# transition_pcb.net
KiCad netlist of a schematic drawn in EAGLE
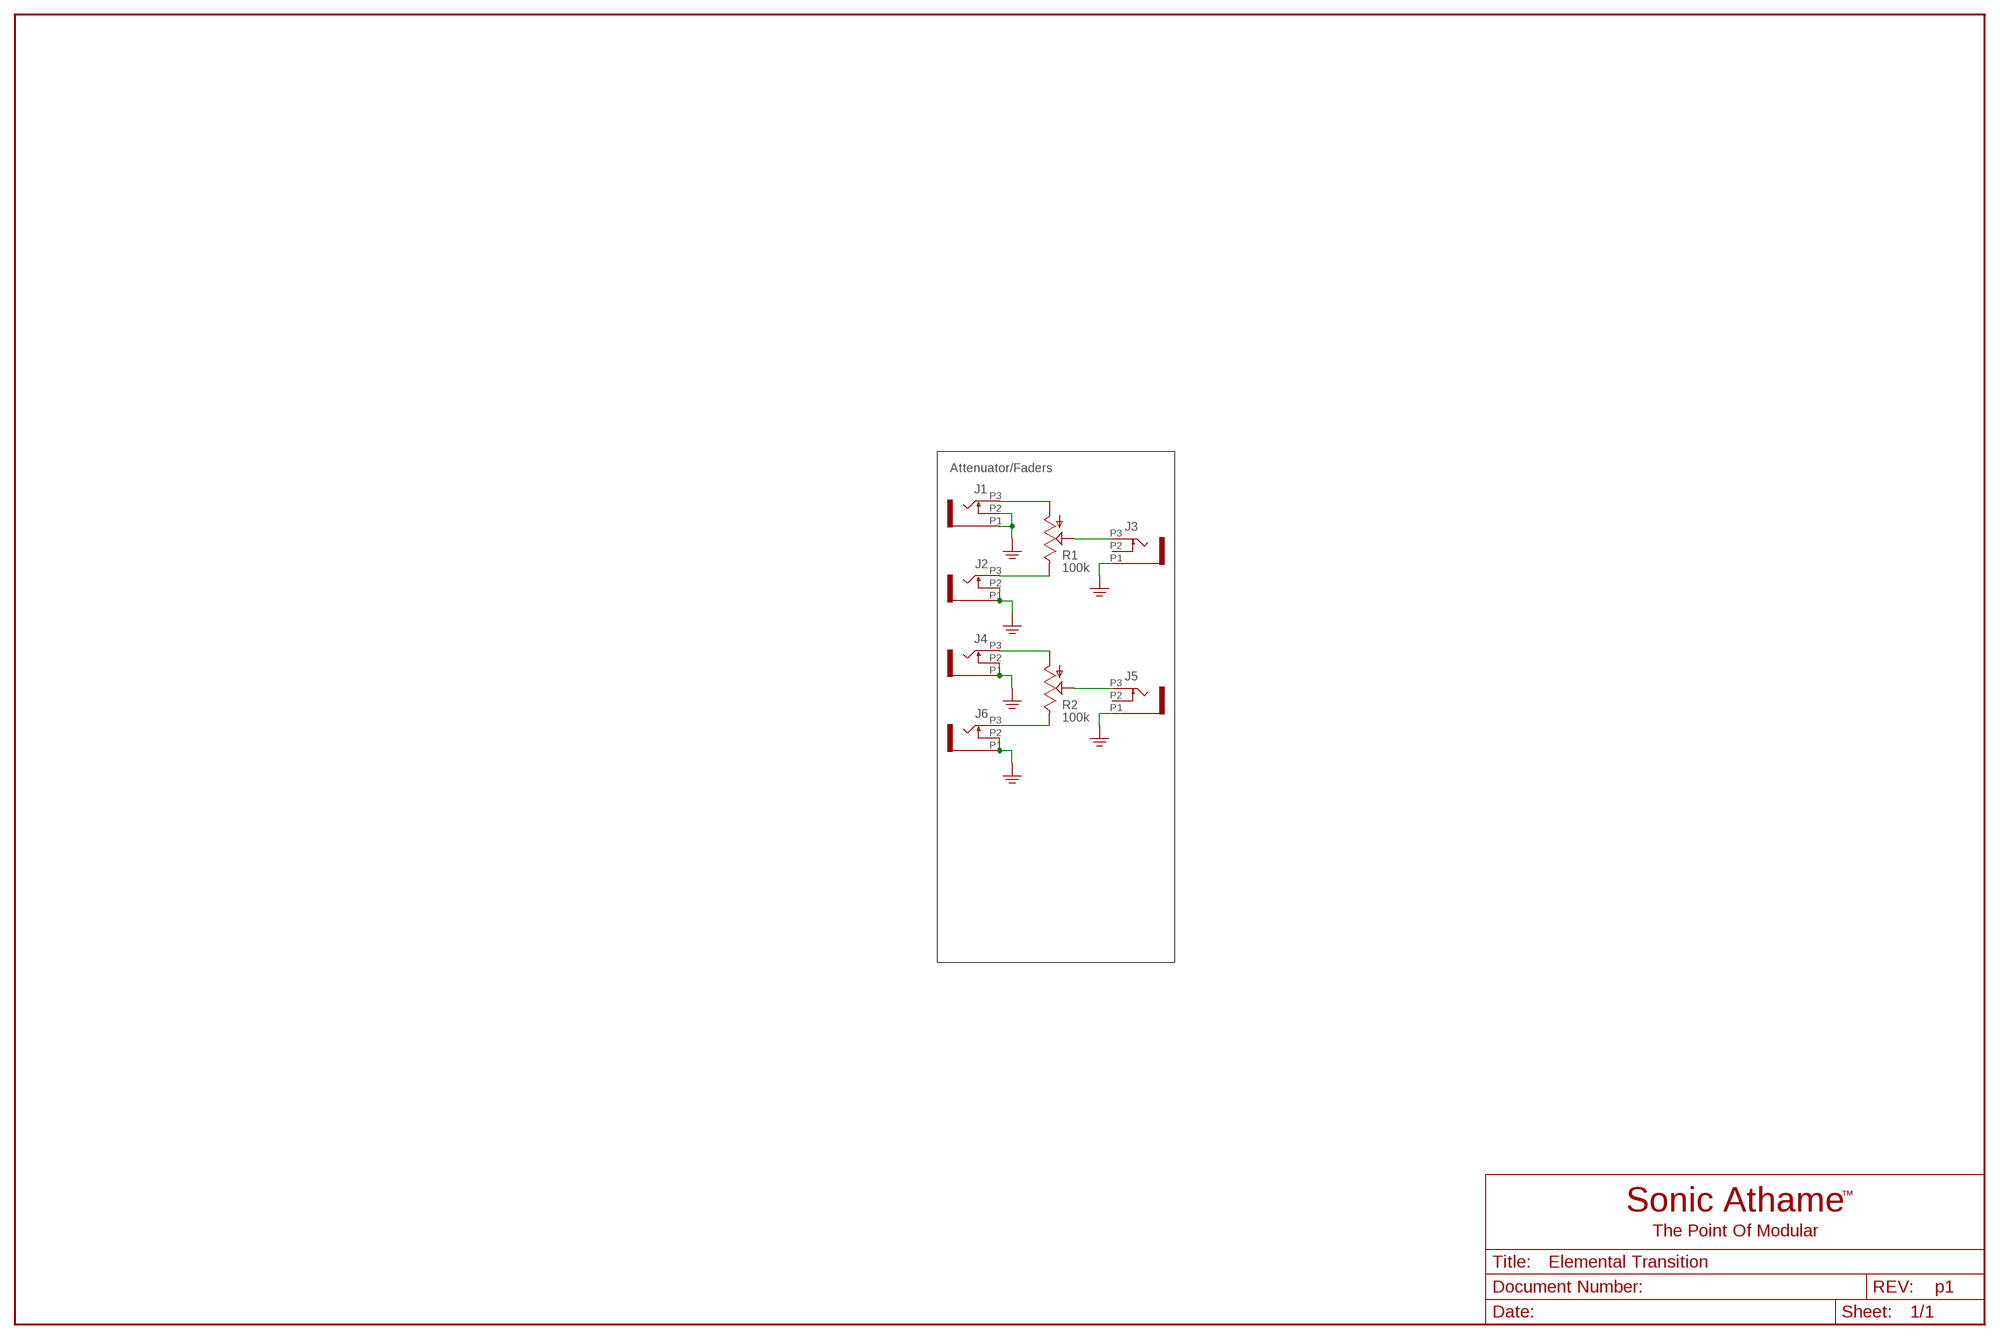
[diagram p0: schematic, sheet 1]

(export (version "E")
  (design (tool "Eeschema 10.0.6"))
  (components
    (comp (ref "J1")
      (value "WQP-PJ398SM6")
      (footprint "eagle-import:WQP_PJ_301M6")
      (libsource (lib "eagle-import") (part "WQP-PJ398SM6"))
    )
    (comp (ref "J2")
      (value "WQP-PJ398SM6")
      (footprint "eagle-import:WQP_PJ_301M6")
      (libsource (lib "eagle-import") (part "WQP-PJ398SM6"))
    )
    (comp (ref "J3")
      (value "WQP-PJ398SM6")
      (footprint "eagle-import:WQP_PJ_301M6")
      (libsource (lib "eagle-import") (part "WQP-PJ398SM6"))
    )
    (comp (ref "J4")
      (value "WQP-PJ398SM6")
      (footprint "eagle-import:WQP_PJ_301M6")
      (libsource (lib "eagle-import") (part "WQP-PJ398SM6"))
    )
    (comp (ref "J5")
      (value "WQP-PJ398SM6")
      (footprint "eagle-import:WQP_PJ_301M6")
      (libsource (lib "eagle-import") (part "WQP-PJ398SM6"))
    )
    (comp (ref "J6")
      (value "WQP-PJ398SM6")
      (footprint "eagle-import:WQP_PJ_301M6")
      (libsource (lib "eagle-import") (part "WQP-PJ398SM6"))
    )
    (comp (ref "R1")
      (value "100k")
      (footprint "eagle-import:ALPHA_POT_VERTICAL")
      (libsource (lib "eagle-import") (part "ALPHA_POT_VERTICALVERTICAL"))
    )
    (comp (ref "R2")
      (value "100k")
      (footprint "eagle-import:ALPHA_POT_VERTICAL")
      (libsource (lib "eagle-import") (part "ALPHA_POT_VERTICALVERTICAL"))
    )
  )
  (nets
    (net (code "1") (name "GND") (class "Default")
      (node (ref "J1") (pin "P1") (pinfunction "1_P1") (pintype "passive"))
      (node (ref "J1") (pin "P2") (pinfunction "2_P2") (pintype "passive"))
      (node (ref "J2") (pin "P1") (pinfunction "1_P1") (pintype "passive"))
      (node (ref "J2") (pin "P2") (pinfunction "2_P2") (pintype "passive"))
      (node (ref "J3") (pin "P1") (pinfunction "1_P1") (pintype "passive"))
      (node (ref "J4") (pin "P1") (pinfunction "1_P1") (pintype "passive"))
      (node (ref "J4") (pin "P2") (pinfunction "2_P2") (pintype "passive"))
      (node (ref "J5") (pin "P1") (pinfunction "1_P1") (pintype "passive"))
      (node (ref "J6") (pin "P1") (pinfunction "1_P1") (pintype "passive"))
      (node (ref "J6") (pin "P2") (pinfunction "2_P2") (pintype "passive"))
    )
    (net (code "2") (name "Net-(J1-3)") (class "Default")
      (node (ref "J1") (pin "P3") (pinfunction "3_P3") (pintype "passive"))
      (node (ref "R1") (pin "P$3") (pinfunction "A_P$3") (pintype "passive"))
    )
    (net (code "3") (name "Net-(J2-3)") (class "Default")
      (node (ref "J2") (pin "P3") (pinfunction "3_P3") (pintype "passive"))
      (node (ref "R1") (pin "P$1") (pinfunction "E_P$1") (pintype "passive"))
    )
    (net (code "4") (name "Net-(J3-3)") (class "Default")
      (node (ref "J3") (pin "P3") (pinfunction "3_P3") (pintype "passive"))
      (node (ref "R1") (pin "P$2") (pinfunction "S_P$2") (pintype "passive"))
    )
    (net (code "5") (name "Net-(J4-3)") (class "Default")
      (node (ref "J4") (pin "P3") (pinfunction "3_P3") (pintype "passive"))
      (node (ref "R2") (pin "P$3") (pinfunction "A_P$3") (pintype "passive"))
    )
    (net (code "6") (name "Net-(J5-3)") (class "Default")
      (node (ref "J5") (pin "P3") (pinfunction "3_P3") (pintype "passive"))
      (node (ref "R2") (pin "P$2") (pinfunction "S_P$2") (pintype "passive"))
    )
    (net (code "7") (name "Net-(J6-3)") (class "Default")
      (node (ref "J6") (pin "P3") (pinfunction "3_P3") (pintype "passive"))
      (node (ref "R2") (pin "P$1") (pinfunction "E_P$1") (pintype "passive"))
    )
    (net (code "8") (name "unconnected-(J3-2-PadP2)") (class "Default")
      (node (ref "J3") (pin "P2") (pinfunction "2_P2") (pintype "passive"))
    )
    (net (code "9") (name "unconnected-(J5-2-PadP2)") (class "Default")
      (node (ref "J5") (pin "P2") (pinfunction "2_P2") (pintype "passive"))
    )
  )
)
